# board1.net
KiCad netlist of a schematic drawn in EAGLE
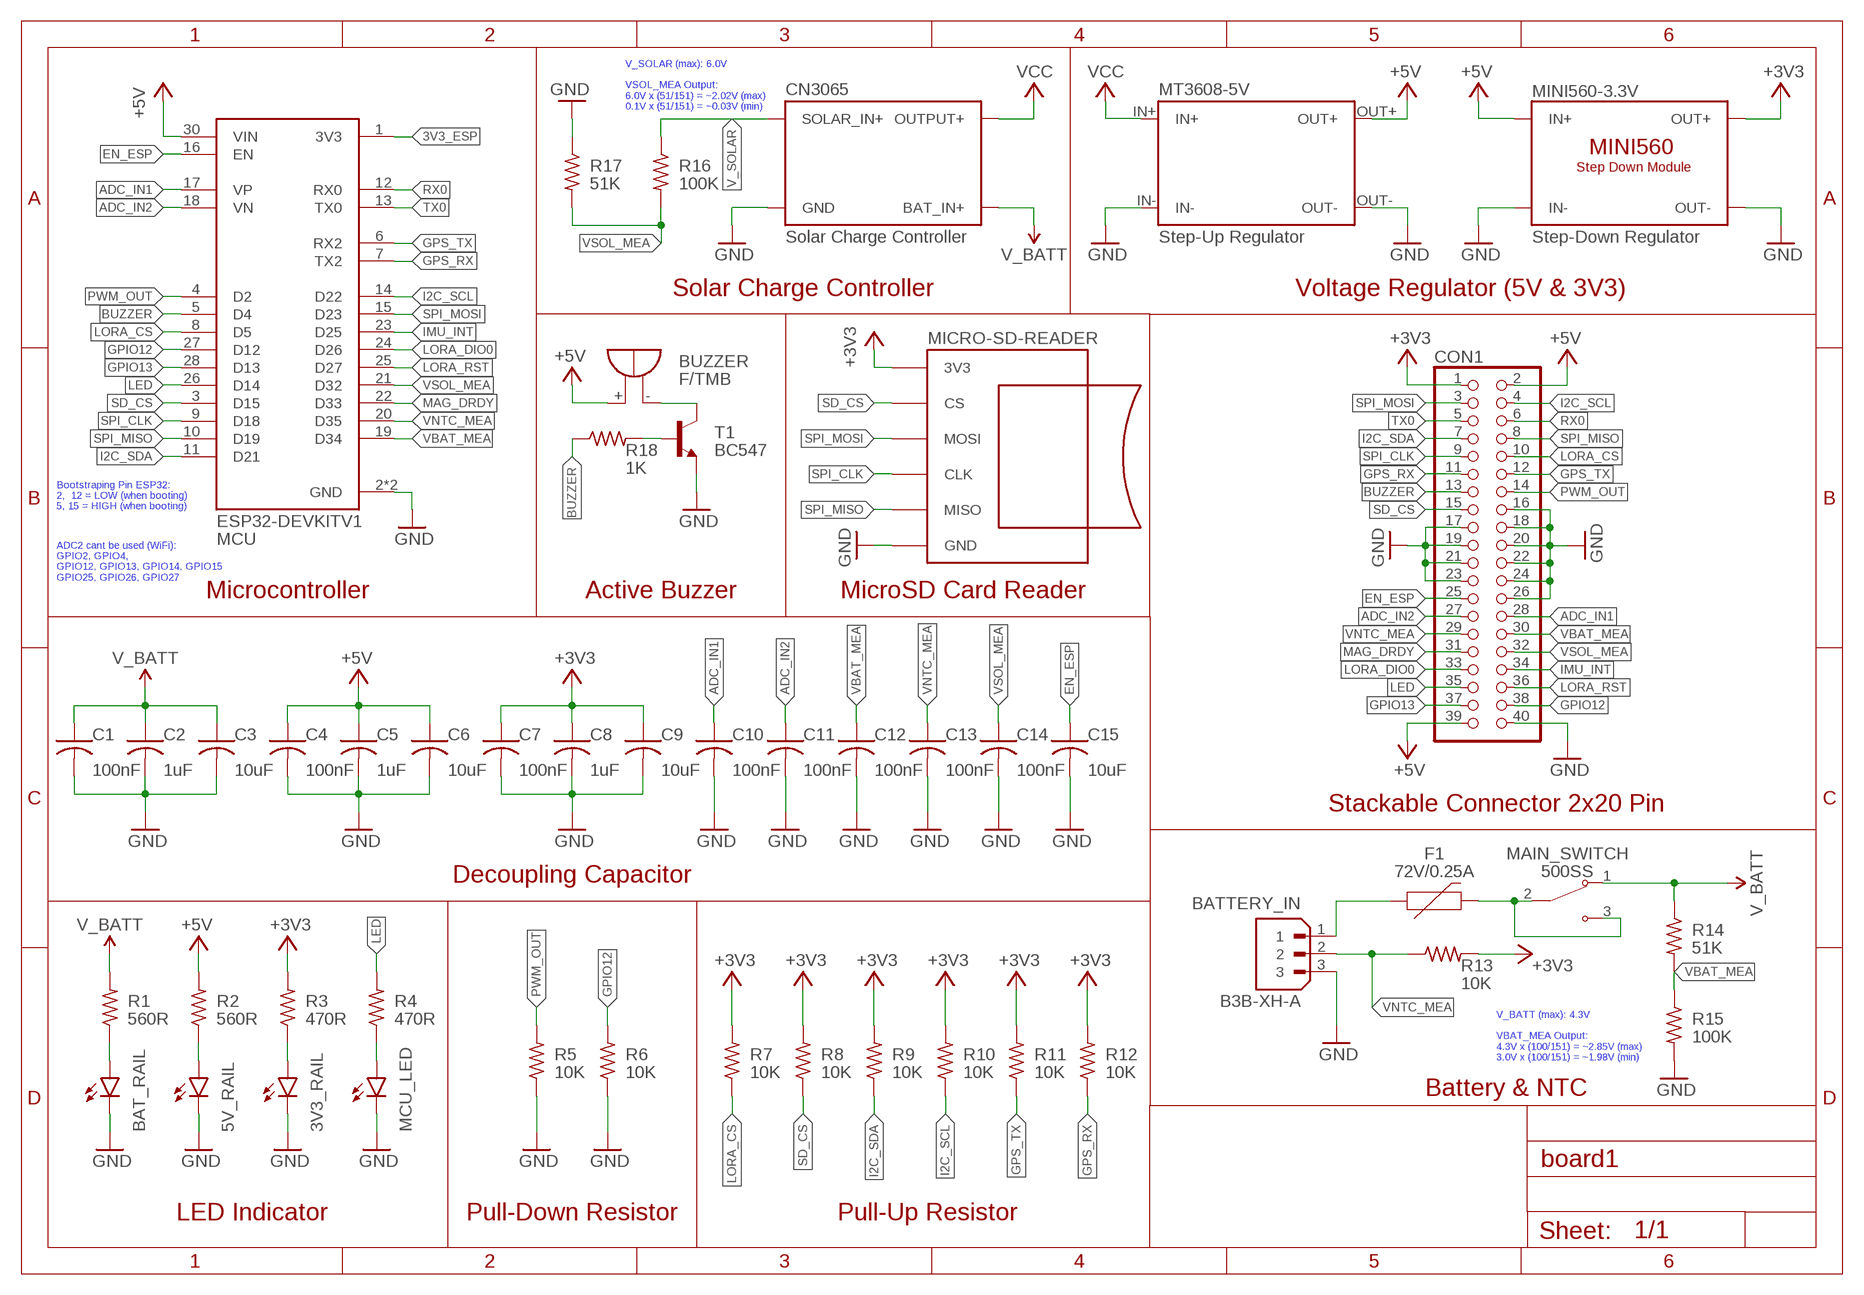
[diagram p0: schematic, sheet 1]

(export (version "E")
  (design (tool "Eeschema 10.0.6"))
  (components
    (comp (ref "3V3_RAIL")
      (value "LEDCHIP-LED0805")
      (footprint "eagle-import:CHIP-LED0805")
      (libsource (lib "eagle-import") (part "LEDCHIP-LED0805"))
    )
    (comp (ref "5V_RAIL")
      (value "LEDCHIP-LED0805")
      (footprint "eagle-import:CHIP-LED0805")
      (libsource (lib "eagle-import") (part "LEDCHIP-LED0805"))
    )
    (comp (ref "BATTERY_IN")
      (value "B3B-XH-A")
      (footprint "eagle-import:JST_B3B-XH-A")
      (fields (field (name "MF") "JST Sales"))
      (libsource (lib "eagle-import") (part "B3B-XH-A"))
    )
    (comp (ref "BAT_RAIL")
      (value "LEDCHIP-LED0805")
      (footprint "eagle-import:CHIP-LED0805")
      (libsource (lib "eagle-import") (part "LEDCHIP-LED0805"))
    )
    (comp (ref "BUZZER")
      (value "F/TMB")
      (footprint "eagle-import:F_TMB")
      (libsource (lib "eagle-import") (part "F/TMB"))
    )
    (comp (ref "C1")
      (value "100nF")
      (footprint "eagle-import:C0805")
      (libsource (lib "eagle-import") (part "C-USC0805"))
    )
    (comp (ref "C2")
      (value "1uF")
      (footprint "eagle-import:C0805")
      (libsource (lib "eagle-import") (part "C-USC0805"))
    )
    (comp (ref "C3")
      (value "10uF")
      (footprint "eagle-import:C0805")
      (libsource (lib "eagle-import") (part "C-USC0805"))
    )
    (comp (ref "C4")
      (value "100nF")
      (footprint "eagle-import:C0805")
      (libsource (lib "eagle-import") (part "C-USC0805"))
    )
    (comp (ref "C5")
      (value "1uF")
      (footprint "eagle-import:C0805")
      (libsource (lib "eagle-import") (part "C-USC0805"))
    )
    (comp (ref "C6")
      (value "10uF")
      (footprint "eagle-import:C0805")
      (libsource (lib "eagle-import") (part "C-USC0805"))
    )
    (comp (ref "C7")
      (value "100nF")
      (footprint "eagle-import:C0805")
      (libsource (lib "eagle-import") (part "C-USC0805"))
    )
    (comp (ref "C8")
      (value "1uF")
      (footprint "eagle-import:C0805")
      (libsource (lib "eagle-import") (part "C-USC0805"))
    )
    (comp (ref "C9")
      (value "10uF")
      (footprint "eagle-import:C0805")
      (libsource (lib "eagle-import") (part "C-USC0805"))
    )
    (comp (ref "C10")
      (value "100nF")
      (footprint "eagle-import:C0805")
      (libsource (lib "eagle-import") (part "C-USC0805"))
    )
    (comp (ref "C11")
      (value "100nF")
      (footprint "eagle-import:C0805")
      (libsource (lib "eagle-import") (part "C-USC0805"))
    )
    (comp (ref "C12")
      (value "100nF")
      (footprint "eagle-import:C0805")
      (libsource (lib "eagle-import") (part "C-USC0805"))
    )
    (comp (ref "C13")
      (value "100nF")
      (footprint "eagle-import:C0805")
      (libsource (lib "eagle-import") (part "C-USC0805"))
    )
    (comp (ref "C14")
      (value "100nF")
      (footprint "eagle-import:C0805")
      (libsource (lib "eagle-import") (part "C-USC0805"))
    )
    (comp (ref "C15")
      (value "10uF")
      (footprint "eagle-import:C0805")
      (libsource (lib "eagle-import") (part "C-USC0805"))
    )
    (comp (ref "CN3065")
      (value "Solar Charge Controller")
      (footprint "eagle-import:CN3065")
      (libsource (lib "eagle-import") (part "CN3065"))
    )
    (comp (ref "CON1")
      (value "PINHD-2X20")
      (footprint "eagle-import:2X20")
      (libsource (lib "eagle-import") (part "PINHD-2X20"))
    )
    (comp (ref "ESP32-DEVKITV1")
      (value "MCU")
      (footprint "eagle-import:MODULE_ESP32_DEVKIT_V1")
      (fields (field (name "MF") "Do it") (field (name "MP") "ESP32-DEVKIT-V1"))
      (libsource (lib "eagle-import") (part "ESP32-DEVKIT-V1"))
    )
    (comp (ref "F1")
      (value "72V/0.25A")
      (footprint "eagle-import:PTH")
      (libsource (lib "eagle-import") (part "PPTC_PTH"))
    )
    (comp (ref "MAIN_SWITCH")
      (value "500SS")
      (footprint "eagle-import:SW_500SSP1S1M2REA")
      (fields (field (name "MF") "E-Switch") (field (name "MP") "500SSP1S1M2REA"))
      (libsource (lib "eagle-import") (part "500SSP1S1M2REA"))
    )
    (comp (ref "MCU_LED")
      (value "LEDCHIP-LED0805")
      (footprint "eagle-import:CHIP-LED0805")
      (libsource (lib "eagle-import") (part "LEDCHIP-LED0805"))
    )
    (comp (ref "MICRO-SD-READER")
      (value "MICROSD-READERUP-TOP")
      (footprint "eagle-import:MICROSD-READER-FACING_UP(TOP_LAYER)")
      (libsource (lib "eagle-import") (part "MICROSD-READERUP-TOP"))
    )
    (comp (ref "MINI560-3.3V")
      (value "Step-Down Regulator")
      (footprint "eagle-import:MINI560-THT")
      (libsource (lib "eagle-import") (part "MINI560_W/O_ENTHT"))
    )
    (comp (ref "MT3608-5V")
      (value "Step-Up Regulator")
      (footprint "eagle-import:MT3608")
      (libsource (lib "eagle-import") (part "MT3608"))
    )
    (comp (ref "R1")
      (value "560R")
      (footprint "eagle-import:R0805")
      (libsource (lib "eagle-import") (part "R-US_R0805"))
    )
    (comp (ref "R2")
      (value "560R")
      (footprint "eagle-import:R0805")
      (libsource (lib "eagle-import") (part "R-US_R0805"))
    )
    (comp (ref "R3")
      (value "470R")
      (footprint "eagle-import:R0805")
      (libsource (lib "eagle-import") (part "R-US_R0805"))
    )
    (comp (ref "R4")
      (value "470R")
      (footprint "eagle-import:R0805")
      (libsource (lib "eagle-import") (part "R-US_R0805"))
    )
    (comp (ref "R5")
      (value "10K")
      (footprint "eagle-import:R0805")
      (libsource (lib "eagle-import") (part "R-US_R0805"))
    )
    (comp (ref "R6")
      (value "10K")
      (footprint "eagle-import:R0805")
      (libsource (lib "eagle-import") (part "R-US_R0805"))
    )
    (comp (ref "R7")
      (value "10K")
      (footprint "eagle-import:R0805")
      (libsource (lib "eagle-import") (part "R-US_R0805"))
    )
    (comp (ref "R8")
      (value "10K")
      (footprint "eagle-import:R0805")
      (libsource (lib "eagle-import") (part "R-US_R0805"))
    )
    (comp (ref "R9")
      (value "10K")
      (footprint "eagle-import:R0805")
      (libsource (lib "eagle-import") (part "R-US_R0805"))
    )
    (comp (ref "R10")
      (value "10K")
      (footprint "eagle-import:R0805")
      (libsource (lib "eagle-import") (part "R-US_R0805"))
    )
    (comp (ref "R11")
      (value "10K")
      (footprint "eagle-import:R0805")
      (libsource (lib "eagle-import") (part "R-US_R0805"))
    )
    (comp (ref "R12")
      (value "10K")
      (footprint "eagle-import:R0805")
      (libsource (lib "eagle-import") (part "R-US_R0805"))
    )
    (comp (ref "R13")
      (value "10K")
      (footprint "eagle-import:R0805")
      (libsource (lib "eagle-import") (part "R-US_R0805"))
    )
    (comp (ref "R14")
      (value "51K")
      (footprint "eagle-import:R0805")
      (libsource (lib "eagle-import") (part "R-US_R0805"))
    )
    (comp (ref "R15")
      (value "100K")
      (footprint "eagle-import:R0805")
      (libsource (lib "eagle-import") (part "R-US_R0805"))
    )
    (comp (ref "R16")
      (value "100K")
      (footprint "eagle-import:R0805")
      (libsource (lib "eagle-import") (part "R-US_R0805"))
    )
    (comp (ref "R17")
      (value "51K")
      (footprint "eagle-import:R0805")
      (libsource (lib "eagle-import") (part "R-US_R0805"))
    )
    (comp (ref "R18")
      (value "1K")
      (footprint "eagle-import:R0805")
      (libsource (lib "eagle-import") (part "R-US_R0805"))
    )
    (comp (ref "T1")
      (value "BC547")
      (footprint "eagle-import:TO92")
      (libsource (lib "eagle-import") (part "BC547"))
    )
  )
  (nets
    (net (code "1") (name "+3V3") (class "Default")
      (node (ref "C7") (pin "1") (pinfunction "1_1") (pintype "passive"))
      (node (ref "C8") (pin "1") (pinfunction "1_1") (pintype "passive"))
      (node (ref "C9") (pin "1") (pinfunction "1_1") (pintype "passive"))
      (node (ref "CON1") (pin "1") (pinfunction "1_1") (pintype "passive"))
      (node (ref "MICRO-SD-READER") (pin "3V3") (pinfunction "3V3_3V3") (pintype "bidirectional"))
      (node (ref "MINI560-3.3V") (pin "1OUT+") (pinfunction "OUT+_1OUT+") (pintype "output"))
      (node (ref "MINI560-3.3V") (pin "2OUT+") (pinfunction "OUT+_2OUT+") (pintype "output"))
      (node (ref "R10") (pin "2") (pinfunction "2_2") (pintype "passive"))
      (node (ref "R11") (pin "2") (pinfunction "2_2") (pintype "passive"))
      (node (ref "R12") (pin "2") (pinfunction "2_2") (pintype "passive"))
      (node (ref "R13") (pin "2") (pinfunction "2_2") (pintype "passive"))
      (node (ref "R3") (pin "2") (pinfunction "2_2") (pintype "passive"))
      (node (ref "R7") (pin "2") (pinfunction "2_2") (pintype "passive"))
      (node (ref "R8") (pin "2") (pinfunction "2_2") (pintype "passive"))
      (node (ref "R9") (pin "2") (pinfunction "2_2") (pintype "passive"))
    )
    (net (code "2") (name "+5V") (class "Default")
      (node (ref "BUZZER") (pin "+") (pinfunction "+_+") (pintype "passive"))
      (node (ref "C4") (pin "1") (pinfunction "1_1") (pintype "passive"))
      (node (ref "C5") (pin "1") (pinfunction "1_1") (pintype "passive"))
      (node (ref "C6") (pin "1") (pinfunction "1_1") (pintype "passive"))
      (node (ref "CON1") (pin "2") (pinfunction "2_2") (pintype "passive"))
      (node (ref "CON1") (pin "39") (pinfunction "39_39") (pintype "passive"))
      (node (ref "ESP32-DEVKITV1") (pin "30") (pinfunction "VIN_30") (pintype "input"))
      (node (ref "MINI560-3.3V") (pin "1IN+") (pinfunction "IN+_1IN+") (pintype "input"))
      (node (ref "MINI560-3.3V") (pin "2IN+") (pinfunction "IN+_2IN+") (pintype "input"))
      (node (ref "MT3608-5V") (pin "OUT+") (pinfunction "OUT+_OUT+") (pintype "bidirectional"))
      (node (ref "R2") (pin "2") (pinfunction "2_2") (pintype "passive"))
    )
    (net (code "3") (name "3V3_ESP") (class "Default")
      (node (ref "ESP32-DEVKITV1") (pin "1") (pinfunction "3V3_1") (pintype "output"))
    )
    (net (code "4") (name "ADC_IN1") (class "Default")
      (node (ref "C10") (pin "1") (pinfunction "1_1") (pintype "passive"))
      (node (ref "CON1") (pin "28") (pinfunction "28_28") (pintype "passive"))
      (node (ref "ESP32-DEVKITV1") (pin "17") (pinfunction "VP_17") (pintype "bidirectional"))
    )
    (net (code "5") (name "ADC_IN2") (class "Default")
      (node (ref "C11") (pin "1") (pinfunction "1_1") (pintype "passive"))
      (node (ref "CON1") (pin "27") (pinfunction "27_27") (pintype "passive"))
      (node (ref "ESP32-DEVKITV1") (pin "18") (pinfunction "VN_18") (pintype "bidirectional"))
    )
    (net (code "6") (name "BUZZER") (class "Default")
      (node (ref "CON1") (pin "13") (pinfunction "13_13") (pintype "passive"))
      (node (ref "ESP32-DEVKITV1") (pin "5") (pinfunction "D4_5") (pintype "bidirectional"))
      (node (ref "R18") (pin "1") (pinfunction "1_1") (pintype "passive"))
    )
    (net (code "7") (name "EN_ESP") (class "Default")
      (node (ref "C15") (pin "1") (pinfunction "1_1") (pintype "passive"))
      (node (ref "CON1") (pin "25") (pinfunction "25_25") (pintype "passive"))
      (node (ref "ESP32-DEVKITV1") (pin "16") (pinfunction "EN_16") (pintype "input"))
    )
    (net (code "8") (name "GND") (class "Default")
      (node (ref "3V3_RAIL") (pin "C") (pinfunction "C_C") (pintype "passive"))
      (node (ref "5V_RAIL") (pin "C") (pinfunction "C_C") (pintype "passive"))
      (node (ref "BATTERY_IN") (pin "3") (pinfunction "3_3") (pintype "passive"))
      (node (ref "BAT_RAIL") (pin "C") (pinfunction "C_C") (pintype "passive"))
      (node (ref "C1") (pin "2") (pinfunction "2_2") (pintype "passive"))
      (node (ref "C10") (pin "2") (pinfunction "2_2") (pintype "passive"))
      (node (ref "C11") (pin "2") (pinfunction "2_2") (pintype "passive"))
      (node (ref "C12") (pin "2") (pinfunction "2_2") (pintype "passive"))
      (node (ref "C13") (pin "2") (pinfunction "2_2") (pintype "passive"))
      (node (ref "C14") (pin "2") (pinfunction "2_2") (pintype "passive"))
      (node (ref "C15") (pin "2") (pinfunction "2_2") (pintype "passive"))
      (node (ref "C2") (pin "2") (pinfunction "2_2") (pintype "passive"))
      (node (ref "C3") (pin "2") (pinfunction "2_2") (pintype "passive"))
      (node (ref "C4") (pin "2") (pinfunction "2_2") (pintype "passive"))
      (node (ref "C5") (pin "2") (pinfunction "2_2") (pintype "passive"))
      (node (ref "C6") (pin "2") (pinfunction "2_2") (pintype "passive"))
      (node (ref "C7") (pin "2") (pinfunction "2_2") (pintype "passive"))
      (node (ref "C8") (pin "2") (pinfunction "2_2") (pintype "passive"))
      (node (ref "C9") (pin "2") (pinfunction "2_2") (pintype "passive"))
      (node (ref "CN3065") (pin "BAT-") (pinfunction "GND_BAT-") (pintype "bidirectional"))
      (node (ref "CN3065") (pin "OUT-") (pinfunction "GND_OUT-") (pintype "bidirectional"))
      (node (ref "CN3065") (pin "SC-") (pinfunction "GND_SC-") (pintype "bidirectional"))
      (node (ref "CON1") (pin "16") (pinfunction "16_16") (pintype "passive"))
      (node (ref "CON1") (pin "17") (pinfunction "17_17") (pintype "passive"))
      (node (ref "CON1") (pin "18") (pinfunction "18_18") (pintype "passive"))
      (node (ref "CON1") (pin "19") (pinfunction "19_19") (pintype "passive"))
      (node (ref "CON1") (pin "20") (pinfunction "20_20") (pintype "passive"))
      (node (ref "CON1") (pin "21") (pinfunction "21_21") (pintype "passive"))
      (node (ref "CON1") (pin "22") (pinfunction "22_22") (pintype "passive"))
      (node (ref "CON1") (pin "23") (pinfunction "23_23") (pintype "passive"))
      (node (ref "CON1") (pin "24") (pinfunction "24_24") (pintype "passive"))
      (node (ref "CON1") (pin "26") (pinfunction "26_26") (pintype "passive"))
      (node (ref "CON1") (pin "40") (pinfunction "40_40") (pintype "passive"))
      (node (ref "ESP32-DEVKITV1") (pin "2") (pinfunction "GND_2") (pintype "power_in"))
      (node (ref "ESP32-DEVKITV1") (pin "29") (pinfunction "GND_29") (pintype "power_in"))
      (node (ref "MCU_LED") (pin "C") (pinfunction "C_C") (pintype "passive"))
      (node (ref "MICRO-SD-READER") (pin "GND") (pinfunction "GND_GND") (pintype "bidirectional"))
      (node (ref "MINI560-3.3V") (pin "1IN-") (pinfunction "IN-_1IN-") (pintype "input"))
      (node (ref "MINI560-3.3V") (pin "1OUT-") (pinfunction "OUT-_1OUT-") (pintype "output"))
      (node (ref "MINI560-3.3V") (pin "2IN-") (pinfunction "IN-_2IN-") (pintype "input"))
      (node (ref "MINI560-3.3V") (pin "2OUT-") (pinfunction "OUT-_2OUT-") (pintype "output"))
      (node (ref "MT3608-5V") (pin "IN-") (pinfunction "IN-_IN-") (pintype "bidirectional"))
      (node (ref "MT3608-5V") (pin "OUT-") (pinfunction "OUT-_OUT-") (pintype "bidirectional"))
      (node (ref "R15") (pin "2") (pinfunction "2_2") (pintype "passive"))
      (node (ref "R17") (pin "1") (pinfunction "1_1") (pintype "passive"))
      (node (ref "R5") (pin "1") (pinfunction "1_1") (pintype "passive"))
      (node (ref "R6") (pin "1") (pinfunction "1_1") (pintype "passive"))
      (node (ref "T1") (pin "1") (pinfunction "E_1") (pintype "passive"))
    )
    (net (code "9") (name "GPIO12") (class "Default")
      (node (ref "CON1") (pin "38") (pinfunction "38_38") (pintype "passive"))
      (node (ref "ESP32-DEVKITV1") (pin "27") (pinfunction "D12_27") (pintype "bidirectional"))
      (node (ref "R6") (pin "2") (pinfunction "2_2") (pintype "passive"))
    )
    (net (code "10") (name "GPIO13") (class "Default")
      (node (ref "CON1") (pin "37") (pinfunction "37_37") (pintype "passive"))
      (node (ref "ESP32-DEVKITV1") (pin "28") (pinfunction "D13_28") (pintype "bidirectional"))
    )
    (net (code "11") (name "GPS_RX") (class "Default")
      (node (ref "CON1") (pin "11") (pinfunction "11_11") (pintype "passive"))
      (node (ref "ESP32-DEVKITV1") (pin "7") (pinfunction "TX2_7") (pintype "output"))
      (node (ref "R12") (pin "1") (pinfunction "1_1") (pintype "passive"))
    )
    (net (code "12") (name "GPS_TX") (class "Default")
      (node (ref "CON1") (pin "12") (pinfunction "12_12") (pintype "passive"))
      (node (ref "ESP32-DEVKITV1") (pin "6") (pinfunction "RX2_6") (pintype "input"))
      (node (ref "R11") (pin "1") (pinfunction "1_1") (pintype "passive"))
    )
    (net (code "13") (name "I2C_SCL") (class "Default")
      (node (ref "CON1") (pin "4") (pinfunction "4_4") (pintype "passive"))
      (node (ref "ESP32-DEVKITV1") (pin "14") (pinfunction "D22_14") (pintype "bidirectional"))
      (node (ref "R10") (pin "1") (pinfunction "1_1") (pintype "passive"))
    )
    (net (code "14") (name "I2C_SDA") (class "Default")
      (node (ref "CON1") (pin "7") (pinfunction "7_7") (pintype "passive"))
      (node (ref "ESP32-DEVKITV1") (pin "11") (pinfunction "D21_11") (pintype "bidirectional"))
      (node (ref "R9") (pin "1") (pinfunction "1_1") (pintype "passive"))
    )
    (net (code "15") (name "IMU_INT") (class "Default")
      (node (ref "CON1") (pin "34") (pinfunction "34_34") (pintype "passive"))
      (node (ref "ESP32-DEVKITV1") (pin "23") (pinfunction "D25_23") (pintype "bidirectional"))
    )
    (net (code "16") (name "LED") (class "Default")
      (node (ref "CON1") (pin "35") (pinfunction "35_35") (pintype "passive"))
      (node (ref "ESP32-DEVKITV1") (pin "26") (pinfunction "D14_26") (pintype "bidirectional"))
      (node (ref "R4") (pin "2") (pinfunction "2_2") (pintype "passive"))
    )
    (net (code "17") (name "LORA_CS") (class "Default")
      (node (ref "CON1") (pin "10") (pinfunction "10_10") (pintype "passive"))
      (node (ref "ESP32-DEVKITV1") (pin "8") (pinfunction "D5_8") (pintype "bidirectional"))
      (node (ref "R7") (pin "1") (pinfunction "1_1") (pintype "passive"))
    )
    (net (code "18") (name "LORA_DIO0") (class "Default")
      (node (ref "CON1") (pin "33") (pinfunction "33_33") (pintype "passive"))
      (node (ref "ESP32-DEVKITV1") (pin "24") (pinfunction "D26_24") (pintype "bidirectional"))
    )
    (net (code "19") (name "LORA_RST") (class "Default")
      (node (ref "CON1") (pin "36") (pinfunction "36_36") (pintype "passive"))
      (node (ref "ESP32-DEVKITV1") (pin "25") (pinfunction "D27_25") (pintype "bidirectional"))
    )
    (net (code "20") (name "MAG_DRDY") (class "Default")
      (node (ref "CON1") (pin "31") (pinfunction "31_31") (pintype "passive"))
      (node (ref "ESP32-DEVKITV1") (pin "22") (pinfunction "D33_22") (pintype "bidirectional"))
    )
    (net (code "21") (name "Net-(3V3_RAIL-PadA)") (class "Default")
      (node (ref "3V3_RAIL") (pin "A") (pinfunction "A_A") (pintype "passive"))
      (node (ref "R3") (pin "1") (pinfunction "1_1") (pintype "passive"))
    )
    (net (code "22") (name "Net-(5V_RAIL-PadA)") (class "Default")
      (node (ref "5V_RAIL") (pin "A") (pinfunction "A_A") (pintype "passive"))
      (node (ref "R2") (pin "1") (pinfunction "1_1") (pintype "passive"))
    )
    (net (code "23") (name "Net-(BAT_RAIL-PadA)") (class "Default")
      (node (ref "BAT_RAIL") (pin "A") (pinfunction "A_A") (pintype "passive"))
      (node (ref "R1") (pin "1") (pinfunction "1_1") (pintype "passive"))
    )
    (net (code "24") (name "Net-(F1-1)") (class "Default")
      (node (ref "BATTERY_IN") (pin "1") (pinfunction "1_1") (pintype "passive"))
      (node (ref "F1") (pin "P$1") (pinfunction "1_P$1") (pintype "bidirectional"))
    )
    (net (code "25") (name "Net-(F1-2)") (class "Default")
      (node (ref "F1") (pin "P$2") (pinfunction "2_P$2") (pintype "bidirectional"))
      (node (ref "MAIN_SWITCH") (pin "2") (pinfunction "COM_2") (pintype "passive"))
      (node (ref "MAIN_SWITCH") (pin "3") (pinfunction "NO_3") (pintype "passive"))
    )
    (net (code "26") (name "Net-(MCU_LED-PadA)") (class "Default")
      (node (ref "MCU_LED") (pin "A") (pinfunction "A_A") (pintype "passive"))
      (node (ref "R4") (pin "1") (pinfunction "1_1") (pintype "passive"))
    )
    (net (code "27") (name "Net-(T1-B)") (class "Default")
      (node (ref "R18") (pin "2") (pinfunction "2_2") (pintype "passive"))
      (node (ref "T1") (pin "2") (pinfunction "B_2") (pintype "passive"))
    )
    (net (code "28") (name "Net-(T1-C)") (class "Default")
      (node (ref "BUZZER") (pin "-") (pinfunction "-_-") (pintype "passive"))
      (node (ref "T1") (pin "3") (pinfunction "C_3") (pintype "passive"))
    )
    (net (code "29") (name "PWM_OUT") (class "Default")
      (node (ref "CON1") (pin "14") (pinfunction "14_14") (pintype "passive"))
      (node (ref "ESP32-DEVKITV1") (pin "4") (pinfunction "D2_4") (pintype "bidirectional"))
      (node (ref "R5") (pin "2") (pinfunction "2_2") (pintype "passive"))
    )
    (net (code "30") (name "RX0") (class "Default")
      (node (ref "CON1") (pin "6") (pinfunction "6_6") (pintype "passive"))
      (node (ref "ESP32-DEVKITV1") (pin "12") (pinfunction "RX0_12") (pintype "input"))
    )
    (net (code "31") (name "SD_CS") (class "Default")
      (node (ref "CON1") (pin "15") (pinfunction "15_15") (pintype "passive"))
      (node (ref "ESP32-DEVKITV1") (pin "3") (pinfunction "D15_3") (pintype "bidirectional"))
      (node (ref "MICRO-SD-READER") (pin "CS") (pinfunction "CS_CS") (pintype "bidirectional"))
      (node (ref "R8") (pin "1") (pinfunction "1_1") (pintype "passive"))
    )
    (net (code "32") (name "SPI_CLK") (class "Default")
      (node (ref "CON1") (pin "9") (pinfunction "9_9") (pintype "passive"))
      (node (ref "ESP32-DEVKITV1") (pin "9") (pinfunction "D18_9") (pintype "bidirectional"))
      (node (ref "MICRO-SD-READER") (pin "CLK") (pinfunction "CLK_CLK") (pintype "bidirectional"))
    )
    (net (code "33") (name "SPI_MISO") (class "Default")
      (node (ref "CON1") (pin "8") (pinfunction "8_8") (pintype "passive"))
      (node (ref "ESP32-DEVKITV1") (pin "10") (pinfunction "D19_10") (pintype "bidirectional"))
      (node (ref "MICRO-SD-READER") (pin "MISO") (pinfunction "MISO_MISO") (pintype "bidirectional"))
    )
    (net (code "34") (name "SPI_MOSI") (class "Default")
      (node (ref "CON1") (pin "3") (pinfunction "3_3") (pintype "passive"))
      (node (ref "ESP32-DEVKITV1") (pin "15") (pinfunction "D23_15") (pintype "bidirectional"))
      (node (ref "MICRO-SD-READER") (pin "MOSI") (pinfunction "MOSI_MOSI") (pintype "bidirectional"))
    )
    (net (code "35") (name "TX0") (class "Default")
      (node (ref "CON1") (pin "5") (pinfunction "5_5") (pintype "passive"))
      (node (ref "ESP32-DEVKITV1") (pin "13") (pinfunction "TX0_13") (pintype "output"))
    )
    (net (code "36") (name "VBAT_MEA") (class "Default")
      (node (ref "C12") (pin "1") (pinfunction "1_1") (pintype "passive"))
      (node (ref "CON1") (pin "30") (pinfunction "30_30") (pintype "passive"))
      (node (ref "ESP32-DEVKITV1") (pin "19") (pinfunction "D34_19") (pintype "bidirectional"))
      (node (ref "R14") (pin "2") (pinfunction "2_2") (pintype "passive"))
      (node (ref "R15") (pin "1") (pinfunction "1_1") (pintype "passive"))
    )
    (net (code "37") (name "VCC") (class "Default")
      (node (ref "CN3065") (pin "OUT+") (pinfunction "OUTPUT+_OUT+") (pintype "bidirectional"))
      (node (ref "MT3608-5V") (pin "IN+") (pinfunction "IN+_IN+") (pintype "bidirectional"))
    )
    (net (code "38") (name "VNTC_MEA") (class "Default")
      (node (ref "BATTERY_IN") (pin "2") (pinfunction "2_2") (pintype "passive"))
      (node (ref "C13") (pin "1") (pinfunction "1_1") (pintype "passive"))
      (node (ref "CON1") (pin "29") (pinfunction "29_29") (pintype "passive"))
      (node (ref "ESP32-DEVKITV1") (pin "20") (pinfunction "D35_20") (pintype "bidirectional"))
      (node (ref "R13") (pin "1") (pinfunction "1_1") (pintype "passive"))
    )
    (net (code "39") (name "VSOL_MEA") (class "Default")
      (node (ref "C14") (pin "1") (pinfunction "1_1") (pintype "passive"))
      (node (ref "CON1") (pin "32") (pinfunction "32_32") (pintype "passive"))
      (node (ref "ESP32-DEVKITV1") (pin "21") (pinfunction "D32_21") (pintype "bidirectional"))
      (node (ref "R16") (pin "2") (pinfunction "2_2") (pintype "passive"))
      (node (ref "R17") (pin "2") (pinfunction "2_2") (pintype "passive"))
    )
    (net (code "40") (name "V_BATT") (class "Default")
      (node (ref "C1") (pin "1") (pinfunction "1_1") (pintype "passive"))
      (node (ref "C2") (pin "1") (pinfunction "1_1") (pintype "passive"))
      (node (ref "C3") (pin "1") (pinfunction "1_1") (pintype "passive"))
      (node (ref "CN3065") (pin "BAT+") (pinfunction "BAT_IN+_BAT+") (pintype "bidirectional"))
      (node (ref "MAIN_SWITCH") (pin "1") (pinfunction "NC_1") (pintype "passive"))
      (node (ref "R1") (pin "2") (pinfunction "2_2") (pintype "passive"))
      (node (ref "R14") (pin "1") (pinfunction "1_1") (pintype "passive"))
    )
    (net (code "41") (name "V_SOLAR") (class "Default")
      (node (ref "CN3065") (pin "SC+") (pinfunction "SOLAR_IN+_SC+") (pintype "bidirectional"))
      (node (ref "R16") (pin "1") (pinfunction "1_1") (pintype "passive"))
    )
  )
)
